# feather-power-switch-mk-1_0.net
KiCad netlist of a schematic drawn in EAGLE
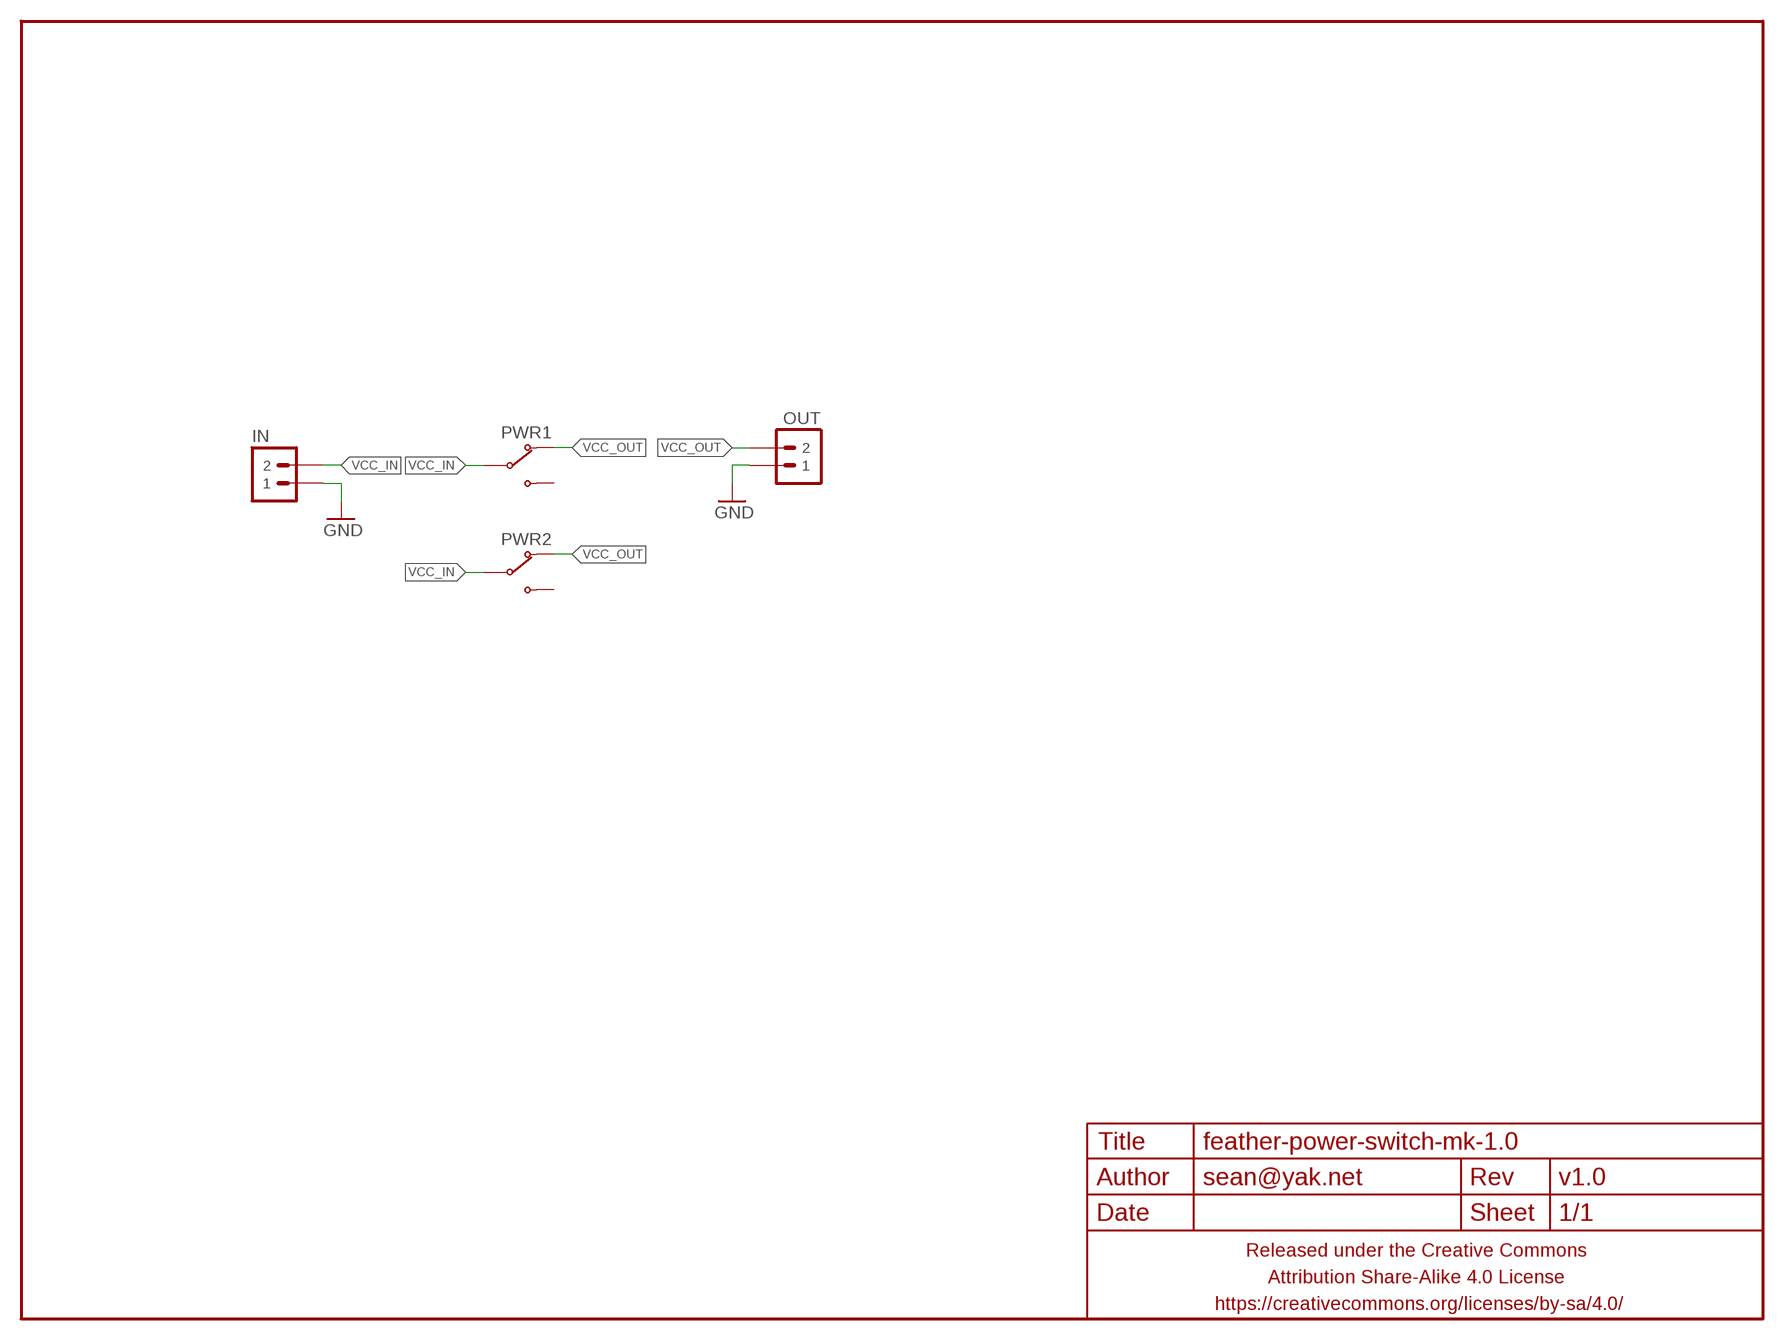
[diagram p0: schematic, sheet 1]

(export (version "E")
  (design (tool "Eeschema 10.0.6"))
  (components
    (comp (ref "FRAME1")
      (value "FRAME-LETTERNO_PACKAGE")
      (footprint "eagle-import:DUMMY")
      (fields (field (name "DESIGNER") "sean@yak.net") (field (name "VERSION") "v1.0"))
      (libsource (lib "eagle-import") (part "FRAME-LETTERNO_PACKAGE"))
    )
    (comp (ref "IN")
      (value "M02JST-PTH-RA-R+")
      (footprint "eagle-import:JST-2-PH-RA-PTH-R+")
      (libsource (lib "eagle-import") (part "M02JST-PTH-RA-R+"))
    )
    (comp (ref "OUT")
      (value "M02PTH-CENTERED-R+")
      (footprint "eagle-import:1X02-CENTER-R+")
      (libsource (lib "eagle-import") (part "M02PTH-CENTERED-R+"))
    )
    (comp (ref "PWR1")
      (value "SWITCH-SPDTPCM12SMTR")
      (footprint "eagle-import:SWITCH-SPDT-SMD-RA-PCM12SMTR")
      (libsource (lib "eagle-import") (part "SWITCH-SPDTPCM12SMTR"))
    )
    (comp (ref "PWR2")
      (value "SWITCH-SPDTPCM12SMTR")
      (footprint "eagle-import:SWITCH-SPDT-SMD-RA-PCM12SMTR")
      (libsource (lib "eagle-import") (part "SWITCH-SPDTPCM12SMTR"))
    )
  )
  (nets
    (net (code "1") (name "GND") (class "Default")
      (node (ref "IN") (pin "1") (pinfunction "1_1") (pintype "passive"))
      (node (ref "OUT") (pin "1") (pinfunction "1_1") (pintype "passive"))
    )
    (net (code "2") (name "VCC_IN") (class "Default")
      (node (ref "IN") (pin "2") (pinfunction "2_2") (pintype "passive"))
      (node (ref "PWR1") (pin "2") (pinfunction "COM_2") (pintype "passive"))
      (node (ref "PWR2") (pin "2") (pinfunction "COM_2") (pintype "passive"))
    )
    (net (code "3") (name "VCC_OUT") (class "Default")
      (node (ref "OUT") (pin "2") (pinfunction "2_2") (pintype "passive"))
      (node (ref "PWR1") (pin "1") (pinfunction "NC_1") (pintype "passive"))
      (node (ref "PWR2") (pin "1") (pinfunction "NC_1") (pintype "passive"))
    )
    (net (code "4") (name "unconnected-(PWR1-NO-Pad3)") (class "Default")
      (node (ref "PWR1") (pin "3") (pinfunction "NO_3") (pintype "passive"))
    )
    (net (code "5") (name "unconnected-(PWR2-NO-Pad3)") (class "Default")
      (node (ref "PWR2") (pin "3") (pinfunction "NO_3") (pintype "passive"))
    )
  )
)
